# link.net
KiCad netlist of a schematic drawn in Altium Designer
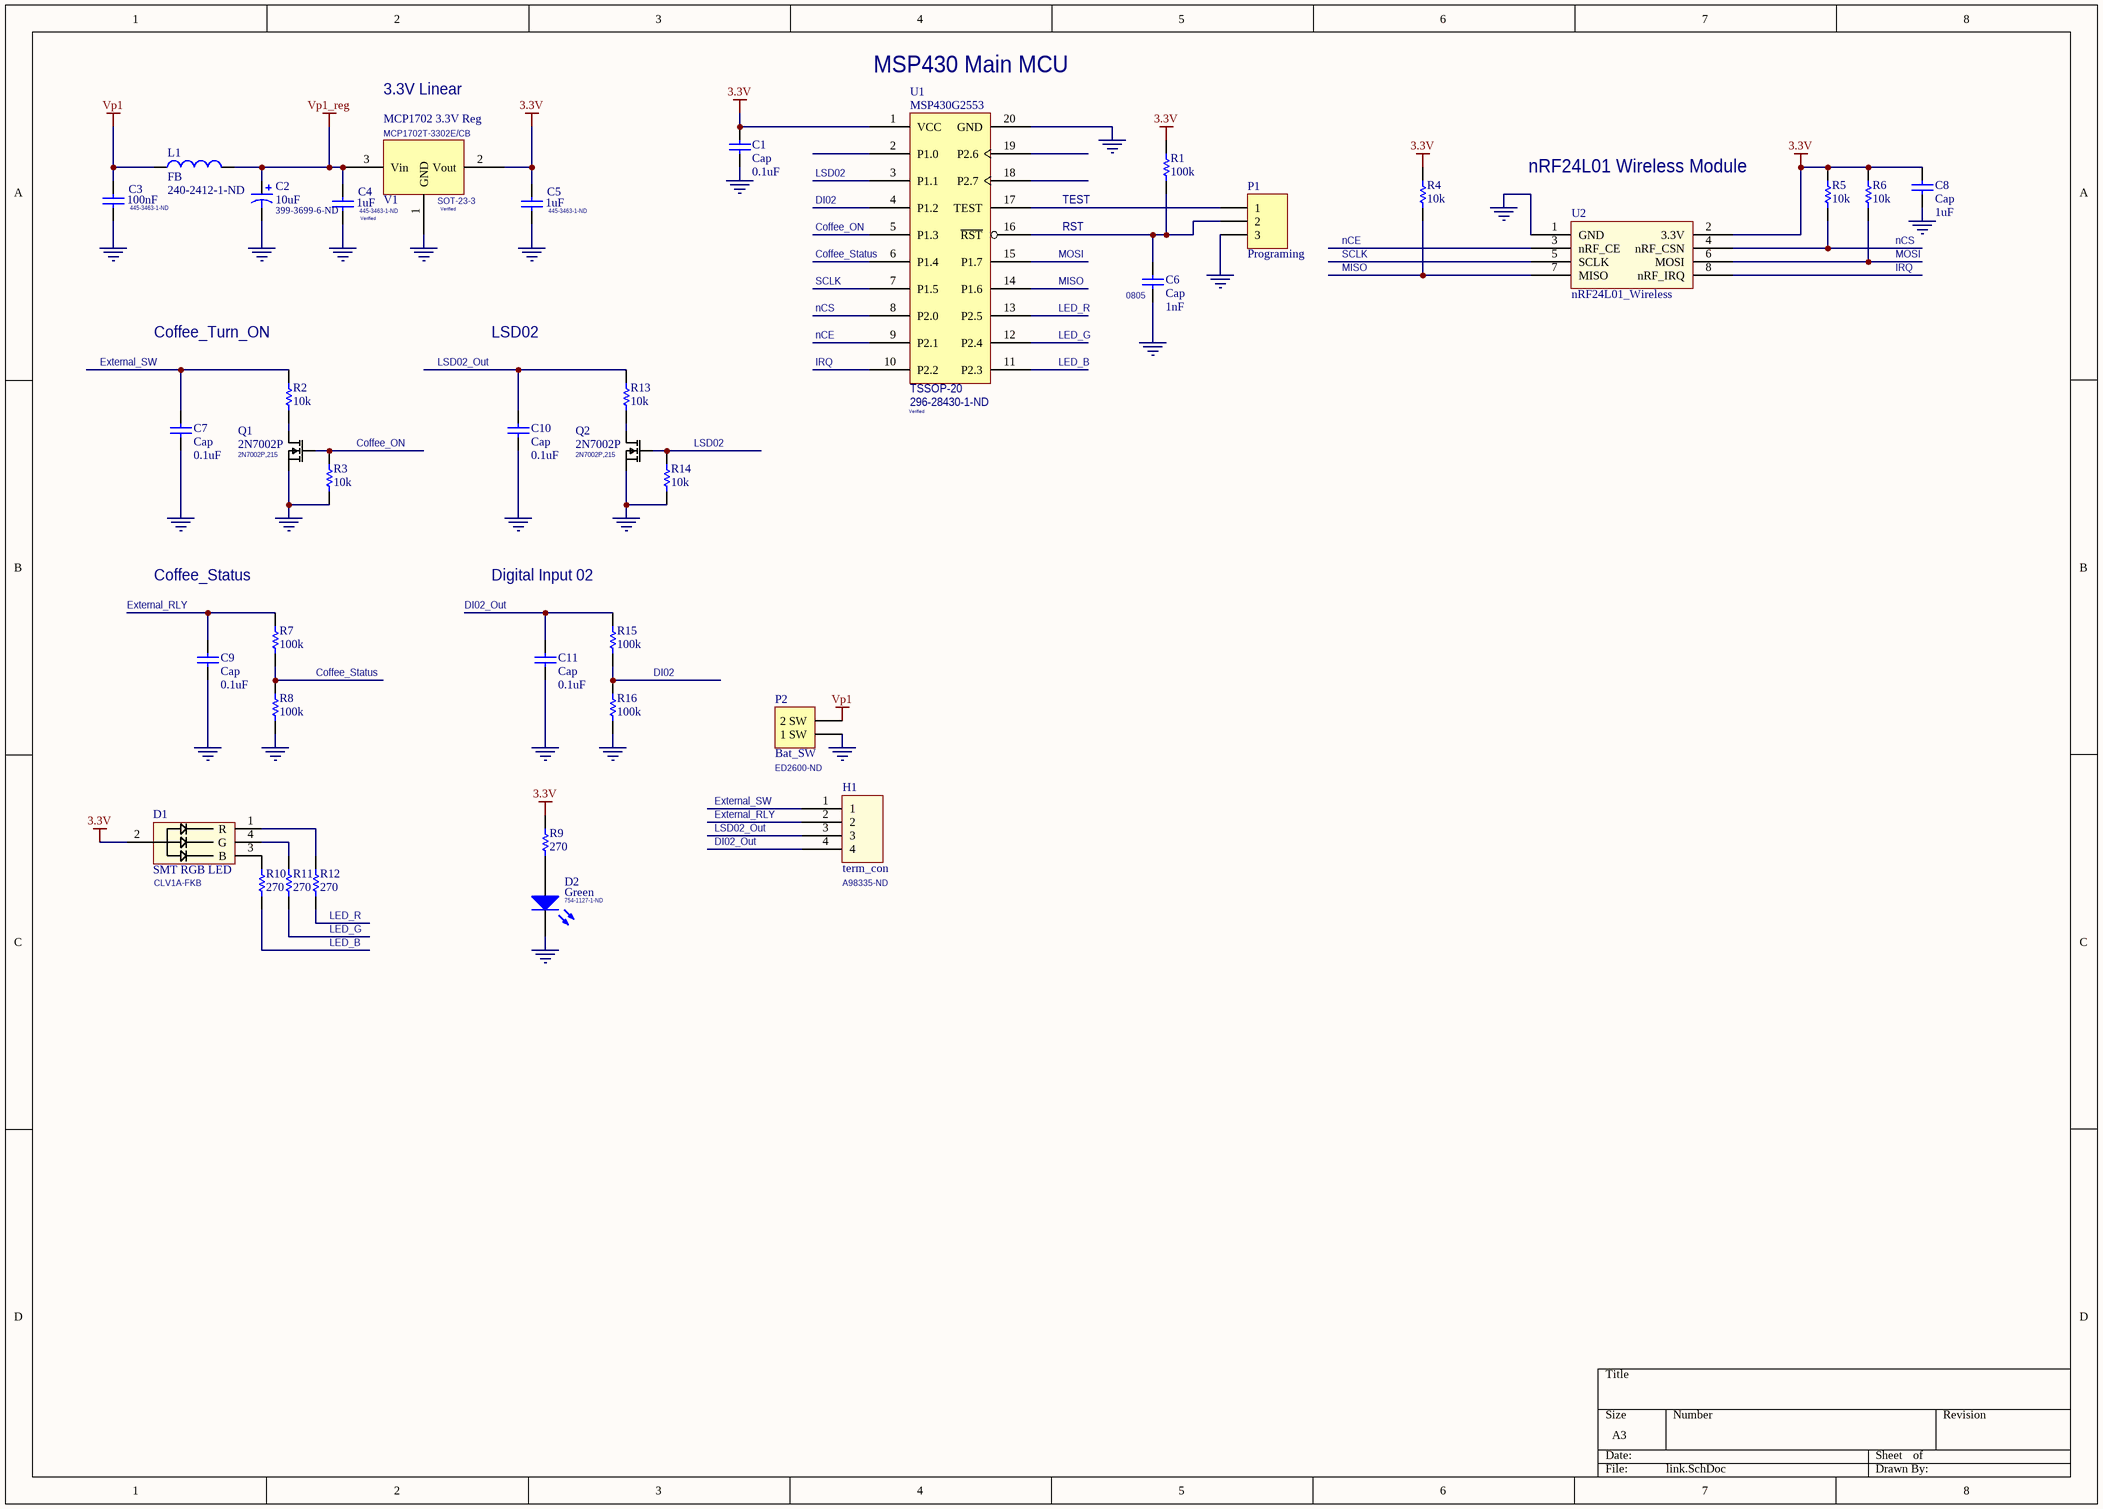
[diagram p0: link.SchDoc]

(export (version "E")
  (design (tool "Eeschema 10.0.6"))
  (components
    (comp (ref "C1")
      (value "Cap")
      (footprint "C0805")
      (description "Capacitor")
      (fields (field (name "ALTIUM_VALUE") "0.1uF") (field (name "PUBLISHER") "Altium Limited"))
      (libsource (lib "Miscellaneous Devices") (part "Cap"))
    )
    (comp (ref "C2")
      (value "10uF")
      (footprint "1206_C")
      (description "Polarized Capacitor (Radial)")
      (fields (field (name "ALTIUM_UNNAMED_1") "399-3699-6-ND") (field (name "Comment") "Cap Pol1"))
      (libsource (lib "Miscellaneous Devices") (part "Cap Pol1"))
    )
    (comp (ref "C3")
      (value "100nF")
      (footprint "C0805")
      (description "Capacitor")
      (fields (field (name "ALTIUM_UNNAMED_1") "445-3463-1-ND") (field (name "Comment") "Cap"))
      (libsource (lib "Miscellaneous Devices") (part "Cap"))
    )
    (comp (ref "C4")
      (value "1uF")
      (footprint "C0805")
      (description "Capacitor")
      (fields (field (name "ALTIUM_UNNAMED_1") "445-3463-1-ND") (field (name "Comment") "Cap"))
      (libsource (lib "Miscellaneous Devices") (part "Cap"))
    )
    (comp (ref "C5")
      (value "1uF")
      (footprint "C0805")
      (description "Capacitor")
      (fields (field (name "ALTIUM_UNNAMED_1") "445-3463-1-ND") (field (name "Comment") "Cap"))
      (libsource (lib "Miscellaneous Devices") (part "Cap"))
    )
    (comp (ref "C6")
      (value "Cap")
      (footprint "C0805")
      (description "Capacitor")
      (fields (field (name "ALTIUM_VALUE") "1nF") (field (name "PUBLISHER") "Altium Limited"))
      (libsource (lib "Miscellaneous Devices") (part "Cap"))
    )
    (comp (ref "C7")
      (value "Cap")
      (footprint "C0805")
      (description "Capacitor")
      (fields (field (name "ALTIUM_VALUE") "0.1uF") (field (name "PUBLISHER") "Altium Limited"))
      (libsource (lib "Miscellaneous Devices") (part "Cap"))
    )
    (comp (ref "C8")
      (value "Cap")
      (footprint "C0805")
      (description "Capacitor")
      (fields (field (name "ALTIUM_VALUE") "1uF") (field (name "PUBLISHER") "Altium Limited"))
      (libsource (lib "Miscellaneous Devices") (part "Cap"))
    )
    (comp (ref "C9")
      (value "Cap")
      (footprint "C0805")
      (description "Capacitor")
      (fields (field (name "ALTIUM_VALUE") "0.1uF") (field (name "PUBLISHER") "Altium Limited"))
      (libsource (lib "Miscellaneous Devices") (part "Cap"))
    )
    (comp (ref "C10")
      (value "Cap")
      (footprint "C0805")
      (description "Capacitor")
      (fields (field (name "ALTIUM_VALUE") "0.1uF") (field (name "PUBLISHER") "Altium Limited"))
      (libsource (lib "Miscellaneous Devices") (part "Cap"))
    )
    (comp (ref "C11")
      (value "Cap")
      (footprint "C0805")
      (description "Capacitor")
      (fields (field (name "ALTIUM_VALUE") "0.1uF") (field (name "PUBLISHER") "Altium Limited"))
      (libsource (lib "Miscellaneous Devices") (part "Cap"))
    )
    (comp (ref "D1")
      (value "SMT RGB LED")
      (footprint "CLV1A-FKB_RGB")
      (fields (field (name "ALTIUM_UNNAMED_1") "CLV1A-FKB"))
      (libsource (lib "RGB_LED") (part "RGB_LED_SMT"))
    )
    (comp (ref "D2")
      (value "LED3")
      (footprint "6-0805_L")
      (description "Typical BLUE SiC LED")
      (fields (field (name "ALTIUM_UNNAMED_1") "Green") (field (name "ALTIUM_UNNAMED_2") "754-1127-1-ND"))
      (libsource (lib "Miscellaneous Devices") (part "LED3"))
    )
    (comp (ref "H1")
      (value "term_con")
      (footprint "A98335-ND")
      (fields (field (name "ALTIUM_UNNAMED_1") "A98335-ND"))
      (libsource (lib "A98335_conz") (part "A98335ND_v1"))
    )
    (comp (ref "L1")
      (value "FB")
      (footprint "1206_IMP")
      (description "Inductor")
      (fields (field (name "ALTIUM_VALUE") "240-2412-1-ND"))
      (libsource (lib "Miscellaneous Devices") (part "Inductor"))
    )
    (comp (ref "P1")
      (value "Programing")
      (footprint "HDR1X3")
      (description "Header, 3-Pin")
      (fields (field (name "PUBLISHER") "Altium Limited"))
      (libsource (lib "Miscellaneous Connectors") (part "Header 3"))
    )
    (comp (ref "P2")
      (value "Bat_SW")
      (footprint "5mm_2TERM")
      (description "Header, 2-Pin")
      (fields (field (name "ALTIUM_UNNAMED_1") "ED2600-ND"))
      (libsource (lib "Miscellaneous Connectors") (part "MHDR1X2"))
    )
    (comp (ref "Q1")
      (value "2N7002P")
      (footprint "SOT-23_M")
      (fields (field (name "ALTIUM_UNNAMED_1") "2N7002P,215"))
      (libsource (lib "2N7002P215") (part "2N7002P"))
    )
    (comp (ref "Q2")
      (value "2N7002P")
      (footprint "SOT-23_M")
      (fields (field (name "ALTIUM_UNNAMED_1") "2N7002P,215"))
      (libsource (lib "2N7002P215") (part "2N7002P"))
    )
    (comp (ref "R1")
      (value "100k")
      (footprint "6-0805_L")
      (description "Resistor")
      (fields (field (name "Comment") "Res1") (field (name "PUBLISHER") "Altium Limited"))
      (libsource (lib "Miscellaneous Devices") (part "Res1"))
    )
    (comp (ref "R2")
      (value "10k")
      (footprint "6-0805_L")
      (description "Resistor")
      (fields (field (name "Comment") "Res1") (field (name "PUBLISHER") "Altium Limited"))
      (libsource (lib "Miscellaneous Devices") (part "Res1"))
    )
    (comp (ref "R3")
      (value "10k")
      (footprint "6-0805_L")
      (description "Resistor")
      (fields (field (name "Comment") "Res1") (field (name "PUBLISHER") "Altium Limited"))
      (libsource (lib "Miscellaneous Devices") (part "Res1"))
    )
    (comp (ref "R4")
      (value "10k")
      (footprint "6-0805_L")
      (description "Resistor")
      (fields (field (name "Comment") "Res1") (field (name "PUBLISHER") "Altium Limited"))
      (libsource (lib "Miscellaneous Devices") (part "Res1"))
    )
    (comp (ref "R5")
      (value "10k")
      (footprint "6-0805_L")
      (description "Resistor")
      (fields (field (name "Comment") "Res1") (field (name "PUBLISHER") "Altium Limited"))
      (libsource (lib "Miscellaneous Devices") (part "Res1"))
    )
    (comp (ref "R6")
      (value "10k")
      (footprint "6-0805_L")
      (description "Resistor")
      (fields (field (name "Comment") "Res1") (field (name "PUBLISHER") "Altium Limited"))
      (libsource (lib "Miscellaneous Devices") (part "Res1"))
    )
    (comp (ref "R7")
      (value "100k")
      (footprint "6-0805_L")
      (description "Resistor")
      (fields (field (name "Comment") "Res1") (field (name "PUBLISHER") "Altium Limited"))
      (libsource (lib "Miscellaneous Devices") (part "Res1"))
    )
    (comp (ref "R8")
      (value "100k")
      (footprint "6-0805_L")
      (description "Resistor")
      (fields (field (name "Comment") "Res1") (field (name "PUBLISHER") "Altium Limited"))
      (libsource (lib "Miscellaneous Devices") (part "Res1"))
    )
    (comp (ref "R9")
      (value "270")
      (footprint "6-0805_L")
      (description "Resistor")
      (fields (field (name "Comment") "Res1") (field (name "PUBLISHER") "Altium Limited"))
      (libsource (lib "Miscellaneous Devices") (part "Res1"))
    )
    (comp (ref "R10")
      (value "270")
      (footprint "6-0805_L")
      (description "Resistor")
      (fields (field (name "Comment") "Res1") (field (name "PUBLISHER") "Altium Limited"))
      (libsource (lib "Miscellaneous Devices") (part "Res1"))
    )
    (comp (ref "R11")
      (value "270")
      (footprint "6-0805_L")
      (description "Resistor")
      (fields (field (name "Comment") "Res1") (field (name "PUBLISHER") "Altium Limited"))
      (libsource (lib "Miscellaneous Devices") (part "Res1"))
    )
    (comp (ref "R12")
      (value "270")
      (footprint "6-0805_L")
      (description "Resistor")
      (fields (field (name "Comment") "Res1") (field (name "PUBLISHER") "Altium Limited"))
      (libsource (lib "Miscellaneous Devices") (part "Res1"))
    )
    (comp (ref "R13")
      (value "10k")
      (footprint "6-0805_L")
      (description "Resistor")
      (fields (field (name "Comment") "Res1") (field (name "PUBLISHER") "Altium Limited"))
      (libsource (lib "Miscellaneous Devices") (part "Res1"))
    )
    (comp (ref "R14")
      (value "10k")
      (footprint "6-0805_L")
      (description "Resistor")
      (fields (field (name "Comment") "Res1") (field (name "PUBLISHER") "Altium Limited"))
      (libsource (lib "Miscellaneous Devices") (part "Res1"))
    )
    (comp (ref "R15")
      (value "100k")
      (footprint "6-0805_L")
      (description "Resistor")
      (fields (field (name "Comment") "Res1") (field (name "PUBLISHER") "Altium Limited"))
      (libsource (lib "Miscellaneous Devices") (part "Res1"))
    )
    (comp (ref "R16")
      (value "100k")
      (footprint "6-0805_L")
      (description "Resistor")
      (fields (field (name "Comment") "Res1") (field (name "PUBLISHER") "Altium Limited"))
      (libsource (lib "Miscellaneous Devices") (part "Res1"))
    )
    (comp (ref "U1")
      (value "MSP430G2553")
      (footprint "TSOP65P640-20AM")
      (fields (field (name "PCK") "TSSOP-20") (field (name "PART#") "296-28430-1-ND"))
      (libsource (lib "MSP430G2553") (part "MSP430G2553"))
    )
    (comp (ref "U2")
      (value "nRF24L01_Wireless")
      (footprint "NRF24L01")
      (libsource (lib "nRF24L01_Wireless") (part "nRF24L01_Wireless"))
    )
    (comp (ref "V1")
      (value "MCP1702 3.3V Reg")
      (footprint "SOT-23B_M")
      (description "MCP1700 3.3V REG")
      (libsource (lib "MCP1700") (part "MCP1700"))
    )
  )
  (nets
    (net (code "1") (name "/Coffee_ON") (class "Default")
      (node (ref "Q1") (pin "1") (pinfunction "G_1") (pintype "passive"))
      (node (ref "R3") (pin "1") (pinfunction "1_1") (pintype "passive"))
      (node (ref "U1") (pin "5") (pinfunction "P1.3_5") (pintype "passive"))
    )
    (net (code "2") (name "/Coffee_Status") (class "Default")
      (node (ref "R7") (pin "2") (pinfunction "2_2") (pintype "passive"))
      (node (ref "R8") (pin "1") (pinfunction "1_1") (pintype "passive"))
      (node (ref "U1") (pin "6") (pinfunction "P1.4_6") (pintype "passive"))
    )
    (net (code "3") (name "/DI02") (class "Default")
      (node (ref "R15") (pin "2") (pinfunction "2_2") (pintype "passive"))
      (node (ref "R16") (pin "1") (pinfunction "1_1") (pintype "passive"))
      (node (ref "U1") (pin "4") (pinfunction "P1.2_4") (pintype "passive"))
    )
    (net (code "4") (name "/DI02_Out") (class "Default")
      (node (ref "C11") (pin "2") (pinfunction "2_2") (pintype "passive"))
      (node (ref "H1") (pin "4") (pinfunction "4_4") (pintype "passive"))
      (node (ref "R15") (pin "1") (pinfunction "1_1") (pintype "passive"))
    )
    (net (code "5") (name "/External_RLY") (class "Default")
      (node (ref "C9") (pin "2") (pinfunction "2_2") (pintype "passive"))
      (node (ref "H1") (pin "2") (pinfunction "2_2") (pintype "passive"))
      (node (ref "R7") (pin "1") (pinfunction "1_1") (pintype "passive"))
    )
    (net (code "6") (name "/External_SW") (class "Default")
      (node (ref "C7") (pin "2") (pinfunction "2_2") (pintype "passive"))
      (node (ref "H1") (pin "1") (pinfunction "1_1") (pintype "passive"))
      (node (ref "R2") (pin "1") (pinfunction "1_1") (pintype "passive"))
    )
    (net (code "7") (name "/IRQ") (class "Default")
      (node (ref "U1") (pin "10") (pinfunction "P2.2_10") (pintype "passive"))
      (node (ref "U2") (pin "8") (pinfunction "nRF_IRQ_8") (pintype "passive"))
    )
    (net (code "8") (name "/LED_B") (class "Default")
      (node (ref "R10") (pin "2") (pinfunction "2_2") (pintype "passive"))
      (node (ref "U1") (pin "11") (pinfunction "P2.3_11") (pintype "passive"))
    )
    (net (code "9") (name "/LED_G") (class "Default")
      (node (ref "R11") (pin "2") (pinfunction "2_2") (pintype "passive"))
      (node (ref "U1") (pin "12") (pinfunction "P2.4_12") (pintype "passive"))
    )
    (net (code "10") (name "/LED_R") (class "Default")
      (node (ref "R12") (pin "2") (pinfunction "2_2") (pintype "passive"))
      (node (ref "U1") (pin "13") (pinfunction "P2.5_13") (pintype "passive"))
    )
    (net (code "11") (name "/LSD02") (class "Default")
      (node (ref "Q2") (pin "1") (pinfunction "G_1") (pintype "passive"))
      (node (ref "R14") (pin "1") (pinfunction "1_1") (pintype "passive"))
      (node (ref "U1") (pin "3") (pinfunction "P1.1_3") (pintype "passive"))
    )
    (net (code "12") (name "/LSD02_Out") (class "Default")
      (node (ref "C10") (pin "2") (pinfunction "2_2") (pintype "passive"))
      (node (ref "H1") (pin "3") (pinfunction "3_3") (pintype "passive"))
      (node (ref "R13") (pin "1") (pinfunction "1_1") (pintype "passive"))
    )
    (net (code "13") (name "/MISO") (class "Default")
      (node (ref "R4") (pin "1") (pinfunction "1_1") (pintype "passive"))
      (node (ref "U1") (pin "14") (pinfunction "P1.6_14") (pintype "passive"))
      (node (ref "U2") (pin "7") (pinfunction "MISO_7") (pintype "passive"))
    )
    (net (code "14") (name "/MOSI") (class "Default")
      (node (ref "R6") (pin "1") (pinfunction "1_1") (pintype "passive"))
      (node (ref "U1") (pin "15") (pinfunction "P1.7_15") (pintype "passive"))
      (node (ref "U2") (pin "6") (pinfunction "MOSI_6") (pintype "passive"))
    )
    (net (code "15") (name "/RST") (class "Default")
      (node (ref "C6") (pin "2") (pinfunction "2_2") (pintype "passive"))
      (node (ref "P1") (pin "2") (pinfunction "2_2") (pintype "passive"))
      (node (ref "R1") (pin "2") (pinfunction "2_2") (pintype "passive"))
      (node (ref "U1") (pin "16") (pinfunction "~{RST}_16") (pintype "passive"))
    )
    (net (code "16") (name "/SCLK") (class "Default")
      (node (ref "U1") (pin "7") (pinfunction "P1.5_7") (pintype "passive"))
      (node (ref "U2") (pin "5") (pinfunction "SCLK_5") (pintype "passive"))
    )
    (net (code "17") (name "/TEST") (class "Default")
      (node (ref "P1") (pin "1") (pinfunction "1_1") (pintype "passive"))
      (node (ref "U1") (pin "17") (pinfunction "TEST_17") (pintype "passive"))
    )
    (net (code "18") (name "/nCE") (class "Default")
      (node (ref "U1") (pin "9") (pinfunction "P2.1_9") (pintype "passive"))
      (node (ref "U2") (pin "3") (pinfunction "nRF_CE_3") (pintype "passive"))
    )
    (net (code "19") (name "/nCS") (class "Default")
      (node (ref "R5") (pin "1") (pinfunction "1_1") (pintype "passive"))
      (node (ref "U1") (pin "8") (pinfunction "P2.0_8") (pintype "passive"))
      (node (ref "U2") (pin "4") (pinfunction "nRF_CSN_4") (pintype "passive"))
    )
    (net (code "20") (name "3.3V") (class "Default")
      (node (ref "C1") (pin "2") (pinfunction "2_2") (pintype "passive"))
      (node (ref "C5") (pin "2") (pinfunction "2_2") (pintype "passive"))
      (node (ref "C8") (pin "2") (pinfunction "2_2") (pintype "passive"))
      (node (ref "D1") (pin "2") (pinfunction "V+_2") (pintype "passive"))
      (node (ref "R1") (pin "1") (pinfunction "1_1") (pintype "passive"))
      (node (ref "R4") (pin "2") (pinfunction "2_2") (pintype "passive"))
      (node (ref "R5") (pin "2") (pinfunction "2_2") (pintype "passive"))
      (node (ref "R6") (pin "2") (pinfunction "2_2") (pintype "passive"))
      (node (ref "R9") (pin "1") (pinfunction "1_1") (pintype "passive"))
      (node (ref "U1") (pin "1") (pinfunction "VCC_1") (pintype "passive"))
      (node (ref "U2") (pin "2") (pinfunction "3.3V_2") (pintype "passive"))
      (node (ref "V1") (pin "2") (pinfunction "Vout_2") (pintype "passive"))
    )
    (net (code "21") (name "GND") (class "Default")
      (node (ref "C1") (pin "1") (pinfunction "1_1") (pintype "passive"))
      (node (ref "C10") (pin "1") (pinfunction "1_1") (pintype "passive"))
      (node (ref "C11") (pin "1") (pinfunction "1_1") (pintype "passive"))
      (node (ref "C2") (pin "2") (pinfunction "2_2") (pintype "passive"))
      (node (ref "C3") (pin "1") (pinfunction "1_1") (pintype "passive"))
      (node (ref "C4") (pin "1") (pinfunction "1_1") (pintype "passive"))
      (node (ref "C5") (pin "1") (pinfunction "1_1") (pintype "passive"))
      (node (ref "C6") (pin "1") (pinfunction "1_1") (pintype "passive"))
      (node (ref "C7") (pin "1") (pinfunction "1_1") (pintype "passive"))
      (node (ref "C8") (pin "1") (pinfunction "1_1") (pintype "passive"))
      (node (ref "C9") (pin "1") (pinfunction "1_1") (pintype "passive"))
      (node (ref "D2") (pin "2") (pinfunction "K_2") (pintype "passive"))
      (node (ref "P1") (pin "3") (pinfunction "3_3") (pintype "passive"))
      (node (ref "P2") (pin "1") (pinfunction "1_SW_1") (pintype "passive"))
      (node (ref "Q1") (pin "2") (pinfunction "S_2") (pintype "passive"))
      (node (ref "Q2") (pin "2") (pinfunction "S_2") (pintype "passive"))
      (node (ref "R14") (pin "2") (pinfunction "2_2") (pintype "passive"))
      (node (ref "R16") (pin "2") (pinfunction "2_2") (pintype "passive"))
      (node (ref "R3") (pin "2") (pinfunction "2_2") (pintype "passive"))
      (node (ref "R8") (pin "2") (pinfunction "2_2") (pintype "passive"))
      (node (ref "U1") (pin "20") (pinfunction "GND_20") (pintype "passive"))
      (node (ref "U2") (pin "1") (pinfunction "GND_1") (pintype "passive"))
      (node (ref "V1") (pin "1") (pinfunction "GND_1") (pintype "passive"))
    )
    (net (code "22") (name "Net-(D1-B)") (class "Default")
      (node (ref "D1") (pin "3") (pinfunction "B_3") (pintype "passive"))
      (node (ref "R10") (pin "1") (pinfunction "1_1") (pintype "passive"))
    )
    (net (code "23") (name "Net-(D1-G)") (class "Default")
      (node (ref "D1") (pin "4") (pinfunction "G_4") (pintype "passive"))
      (node (ref "R11") (pin "1") (pinfunction "1_1") (pintype "passive"))
    )
    (net (code "24") (name "Net-(D1-R)") (class "Default")
      (node (ref "D1") (pin "1") (pinfunction "R_1") (pintype "passive"))
      (node (ref "R12") (pin "1") (pinfunction "1_1") (pintype "passive"))
    )
    (net (code "25") (name "Net-(D2-A)") (class "Default")
      (node (ref "D2") (pin "1") (pinfunction "A_1") (pintype "passive"))
      (node (ref "R9") (pin "2") (pinfunction "2_2") (pintype "passive"))
    )
    (net (code "26") (name "Net-(Q1-D)") (class "Default")
      (node (ref "Q1") (pin "3") (pinfunction "D_3") (pintype "passive"))
      (node (ref "R2") (pin "2") (pinfunction "2_2") (pintype "passive"))
    )
    (net (code "27") (name "Net-(Q2-D)") (class "Default")
      (node (ref "Q2") (pin "3") (pinfunction "D_3") (pintype "passive"))
      (node (ref "R13") (pin "2") (pinfunction "2_2") (pintype "passive"))
    )
    (net (code "28") (name "Vp1") (class "Default")
      (node (ref "C3") (pin "2") (pinfunction "2_2") (pintype "passive"))
      (node (ref "L1") (pin "1") (pinfunction "1_1") (pintype "passive"))
      (node (ref "P2") (pin "2") (pinfunction "2_SW_2") (pintype "passive"))
    )
    (net (code "29") (name "Vp1_reg") (class "Default")
      (node (ref "C2") (pin "1") (pinfunction "1_1") (pintype "passive"))
      (node (ref "C4") (pin "2") (pinfunction "2_2") (pintype "passive"))
      (node (ref "L1") (pin "2") (pinfunction "2_2") (pintype "passive"))
      (node (ref "V1") (pin "3") (pinfunction "Vin_3") (pintype "passive"))
    )
    (net (code "30") (name "unconnected-(U1-P1.0-Pad2)") (class "Default")
      (node (ref "U1") (pin "2") (pinfunction "P1.0_2") (pintype "passive"))
    )
    (net (code "31") (name "unconnected-(U1-P2.6-Pad19)") (class "Default")
      (node (ref "U1") (pin "19") (pinfunction "P2.6_19") (pintype "passive"))
    )
    (net (code "32") (name "unconnected-(U1-P2.7-Pad18)") (class "Default")
      (node (ref "U1") (pin "18") (pinfunction "P2.7_18") (pintype "passive"))
    )
  )
)
